# Camera.net
KiCad netlist of a schematic drawn in Altium Designer
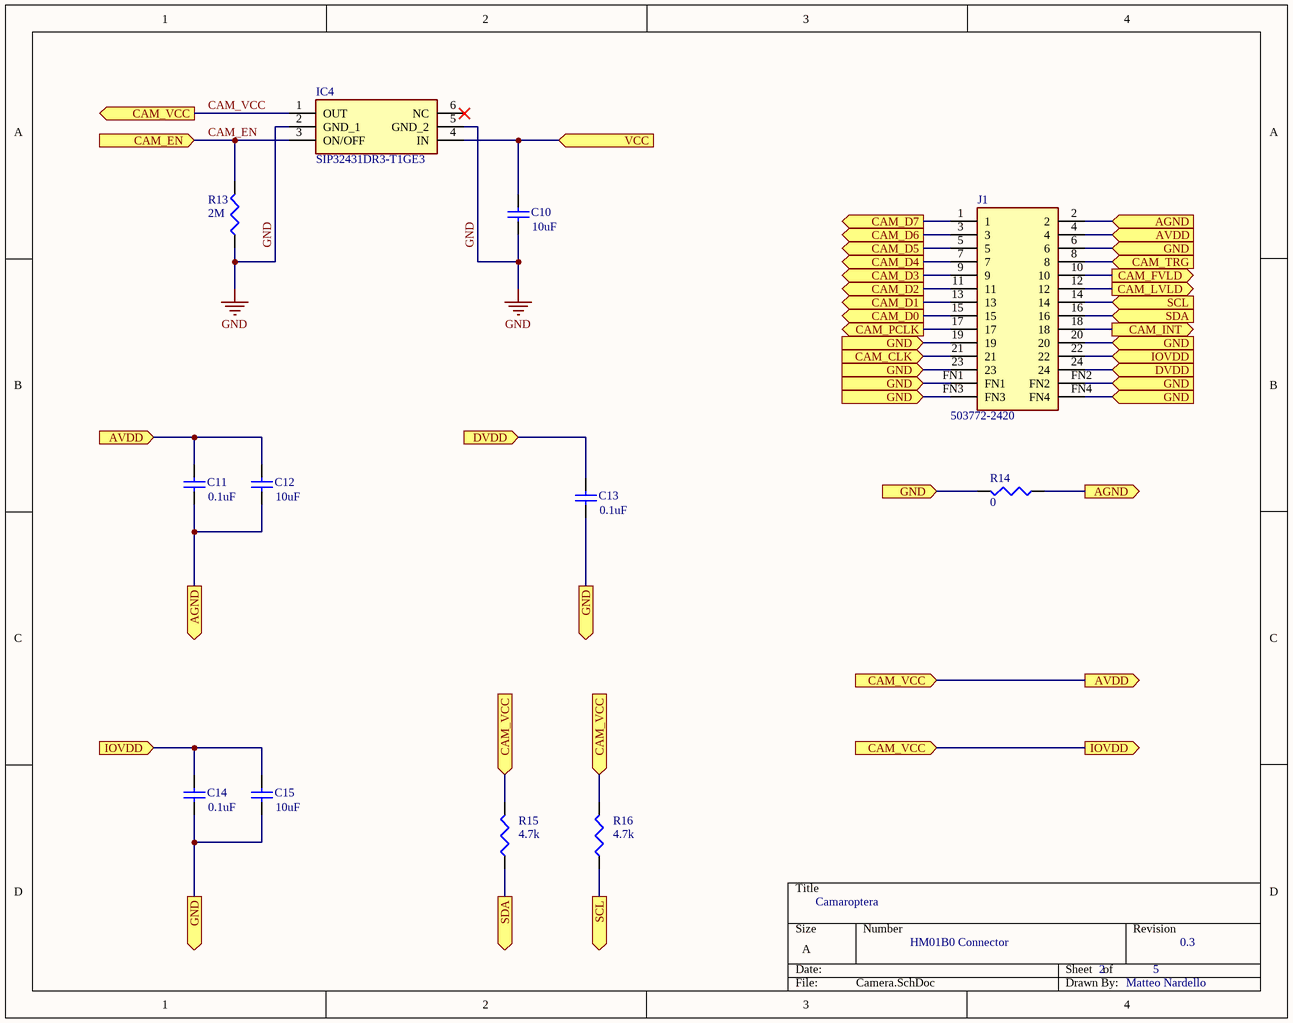
[diagram p0: Camera.SchDoc]

(export (version "E")
  (design (tool "Eeschema 10.0.6"))
  (components
    (comp (ref "C10")
      (value "10uF")
      (footprint "1608[0603]")
      (description "CAP CER 6.3V X5R/X7R 0603")
      (fields (field (name "Comment") "Cap") (field (name "PUBLISHER") "Altium Limited"))
      (libsource (lib "Miscellaneous Devices") (part "Cap"))
    )
    (comp (ref "C11")
      (value "0.1uF")
      (footprint "1608[0603]")
      (description "CAP CER 6.3V X5R/X7R 0603")
      (fields (field (name "Comment") "Cap") (field (name "PUBLISHER") "Altium Limited"))
      (libsource (lib "Miscellaneous Devices") (part "Cap"))
    )
    (comp (ref "C12")
      (value "10uF")
      (footprint "1608[0603]")
      (description "CAP CER 6.3V X5R/X7R 0603")
      (fields (field (name "Comment") "Cap") (field (name "PUBLISHER") "Altium Limited"))
      (libsource (lib "Miscellaneous Devices") (part "Cap"))
    )
    (comp (ref "C13")
      (value "0.1uF")
      (footprint "1608[0603]")
      (description "CAP CER 6.3V X5R/X7R 0603")
      (fields (field (name "Comment") "Cap") (field (name "PUBLISHER") "Altium Limited"))
      (libsource (lib "Miscellaneous Devices") (part "Cap"))
    )
    (comp (ref "C14")
      (value "0.1uF")
      (footprint "1608[0603]")
      (description "CAP CER 6.3V X5R/X7R 0603")
      (fields (field (name "Comment") "Cap") (field (name "PUBLISHER") "Altium Limited"))
      (libsource (lib "Miscellaneous Devices") (part "Cap"))
    )
    (comp (ref "C15")
      (value "10uF")
      (footprint "1608[0603]")
      (description "CAP CER 6.3V X5R/X7R 0603")
      (fields (field (name "Comment") "Cap") (field (name "PUBLISHER") "Altium Limited"))
      (libsource (lib "Miscellaneous Devices") (part "Cap"))
    )
    (comp (ref "IC4")
      (value "SIP32431DR3-T1GE3")
      (footprint "SamacSys:SOT65P210X110-6N")
      (description "10 pA, Ultra Low Leakage and Quiescent Current,\r\nLoad Switch with Reverse Blocking")
      (fields (field (name "MOUSER PART NUMBER") "781-SIP32431DR3-GE3"))
      (libsource (lib "*") (part "SIP32431DR3-T1GE3"))
    )
    (comp (ref "J1")
      (value "503772-2420")
      (footprint "SamacSys:5037722410")
      (fields
        (field (name "MOUSER PART NUMBER") "538-503772-2410")
        (field (name "MANUFACTURER_PART_NUMBER") "503772-2410")
      )
      (libsource (lib "*") (part "503772-2410"))
    )
    (comp (ref "R13")
      (value "2M")
      (footprint "J1-0603")
      (description "RES 1/10W 1% 0603 SMD")
      (fields (field (name "Comment") "Res3") (field (name "PUBLISHER") "Altium Limited"))
      (libsource (lib "Miscellaneous Devices") (part "Res3"))
    )
    (comp (ref "R14")
      (value "0")
      (footprint "J1-0603")
      (description "RES 1/10W 1% 0603 SMD")
      (fields (field (name "Comment") "Res3") (field (name "PUBLISHER") "Altium Limited"))
      (libsource (lib "Miscellaneous Devices") (part "Res3"))
    )
    (comp (ref "R15")
      (value "4.7k")
      (footprint "J1-0603")
      (description "RES 1/10W 1% 0603 SMD")
      (fields (field (name "Comment") "Res3") (field (name "PUBLISHER") "Altium Limited"))
      (libsource (lib "Miscellaneous Devices") (part "Res3"))
    )
    (comp (ref "R16")
      (value "4.7k")
      (footprint "J1-0603")
      (description "RES 1/10W 1% 0603 SMD")
      (fields (field (name "Comment") "Res3") (field (name "PUBLISHER") "Altium Limited"))
      (libsource (lib "Miscellaneous Devices") (part "Res3"))
    )
  )
  (nets
    (net (code "1") (name "/AGND") (class "Default")
      (node (ref "C11") (pin "1") (pinfunction "1_1") (pintype "passive"))
      (node (ref "C12") (pin "1") (pinfunction "1_1") (pintype "passive"))
      (node (ref "J1") (pin "2") (pinfunction "2_2") (pintype "passive"))
      (node (ref "R14") (pin "1") (pinfunction "1_1") (pintype "passive"))
    )
    (net (code "2") (name "/CAM_CLK") (class "Default")
      (node (ref "J1") (pin "21") (pinfunction "21_21") (pintype "passive"))
    )
    (net (code "3") (name "/CAM_D0") (class "Default")
      (node (ref "J1") (pin "15") (pinfunction "15_15") (pintype "passive"))
    )
    (net (code "4") (name "/CAM_D1") (class "Default")
      (node (ref "J1") (pin "13") (pinfunction "13_13") (pintype "passive"))
    )
    (net (code "5") (name "/CAM_D2") (class "Default")
      (node (ref "J1") (pin "11") (pinfunction "11_11") (pintype "passive"))
    )
    (net (code "6") (name "/CAM_D3") (class "Default")
      (node (ref "J1") (pin "9") (pinfunction "9_9") (pintype "passive"))
    )
    (net (code "7") (name "/CAM_D4") (class "Default")
      (node (ref "J1") (pin "7") (pinfunction "7_7") (pintype "passive"))
    )
    (net (code "8") (name "/CAM_D5") (class "Default")
      (node (ref "J1") (pin "5") (pinfunction "5_5") (pintype "passive"))
    )
    (net (code "9") (name "/CAM_D6") (class "Default")
      (node (ref "J1") (pin "3") (pinfunction "3_3") (pintype "passive"))
    )
    (net (code "10") (name "/CAM_D7") (class "Default")
      (node (ref "J1") (pin "1") (pinfunction "1_1") (pintype "passive"))
    )
    (net (code "11") (name "/CAM_EN") (class "Default")
      (node (ref "IC4") (pin "3") (pinfunction "ON/OFF_3") (pintype "passive"))
      (node (ref "R13") (pin "2") (pinfunction "2_2") (pintype "passive"))
    )
    (net (code "12") (name "/CAM_FVLD") (class "Default")
      (node (ref "J1") (pin "10") (pinfunction "10_10") (pintype "passive"))
    )
    (net (code "13") (name "/CAM_INT") (class "Default")
      (node (ref "J1") (pin "18") (pinfunction "18_18") (pintype "passive"))
    )
    (net (code "14") (name "/CAM_LVLD") (class "Default")
      (node (ref "J1") (pin "12") (pinfunction "12_12") (pintype "passive"))
    )
    (net (code "15") (name "/CAM_PCLK") (class "Default")
      (node (ref "J1") (pin "17") (pinfunction "17_17") (pintype "passive"))
    )
    (net (code "16") (name "/CAM_TRG") (class "Default")
      (node (ref "J1") (pin "8") (pinfunction "8_8") (pintype "passive"))
    )
    (net (code "17") (name "/CAM_VCC") (class "Default")
      (node (ref "C11") (pin "2") (pinfunction "2_2") (pintype "passive"))
      (node (ref "C12") (pin "2") (pinfunction "2_2") (pintype "passive"))
      (node (ref "C14") (pin "2") (pinfunction "2_2") (pintype "passive"))
      (node (ref "C15") (pin "2") (pinfunction "2_2") (pintype "passive"))
      (node (ref "IC4") (pin "1") (pinfunction "OUT_1") (pintype "passive"))
      (node (ref "J1") (pin "22") (pinfunction "22_22") (pintype "passive"))
      (node (ref "J1") (pin "4") (pinfunction "4_4") (pintype "passive"))
      (node (ref "R15") (pin "2") (pinfunction "2_2") (pintype "passive"))
      (node (ref "R16") (pin "2") (pinfunction "2_2") (pintype "passive"))
    )
    (net (code "18") (name "/DVDD") (class "Default")
      (node (ref "C13") (pin "2") (pinfunction "2_2") (pintype "passive"))
      (node (ref "J1") (pin "24") (pinfunction "24_24") (pintype "passive"))
    )
    (net (code "19") (name "/SCL") (class "Default")
      (node (ref "J1") (pin "14") (pinfunction "14_14") (pintype "passive"))
      (node (ref "R16") (pin "1") (pinfunction "1_1") (pintype "passive"))
    )
    (net (code "20") (name "/SDA") (class "Default")
      (node (ref "J1") (pin "16") (pinfunction "16_16") (pintype "passive"))
      (node (ref "R15") (pin "1") (pinfunction "1_1") (pintype "passive"))
    )
    (net (code "21") (name "/VCC") (class "Default")
      (node (ref "C10") (pin "2") (pinfunction "2_2") (pintype "passive"))
      (node (ref "IC4") (pin "4") (pinfunction "IN_4") (pintype "passive"))
    )
    (net (code "22") (name "GND") (class "Default")
      (node (ref "C10") (pin "1") (pinfunction "1_1") (pintype "passive"))
      (node (ref "C13") (pin "1") (pinfunction "1_1") (pintype "passive"))
      (node (ref "C14") (pin "1") (pinfunction "1_1") (pintype "passive"))
      (node (ref "C15") (pin "1") (pinfunction "1_1") (pintype "passive"))
      (node (ref "IC4") (pin "2") (pinfunction "GND_1_2") (pintype "passive"))
      (node (ref "IC4") (pin "5") (pinfunction "GND_2_5") (pintype "passive"))
      (node (ref "J1") (pin "19") (pinfunction "19_19") (pintype "passive"))
      (node (ref "J1") (pin "20") (pinfunction "20_20") (pintype "passive"))
      (node (ref "J1") (pin "23") (pinfunction "23_23") (pintype "passive"))
      (node (ref "J1") (pin "6") (pinfunction "6_6") (pintype "passive"))
      (node (ref "J1") (pin "FN1") (pinfunction "FN1_FN1") (pintype "passive"))
      (node (ref "J1") (pin "FN2") (pinfunction "FN2_FN2") (pintype "passive"))
      (node (ref "J1") (pin "FN3") (pinfunction "FN3_FN3") (pintype "passive"))
      (node (ref "J1") (pin "FN4") (pinfunction "FN4_FN4") (pintype "passive"))
      (node (ref "R13") (pin "1") (pinfunction "1_1") (pintype "passive"))
      (node (ref "R14") (pin "2") (pinfunction "2_2") (pintype "passive"))
    )
    (net (code "23") (name "unconnected-(IC4-NC-Pad6)") (class "Default")
      (node (ref "IC4") (pin "6") (pinfunction "NC_6") (pintype "passive+no_connect"))
    )
  )
)
